# balloon-v06.net
KiCad netlist of a schematic drawn in EAGLE
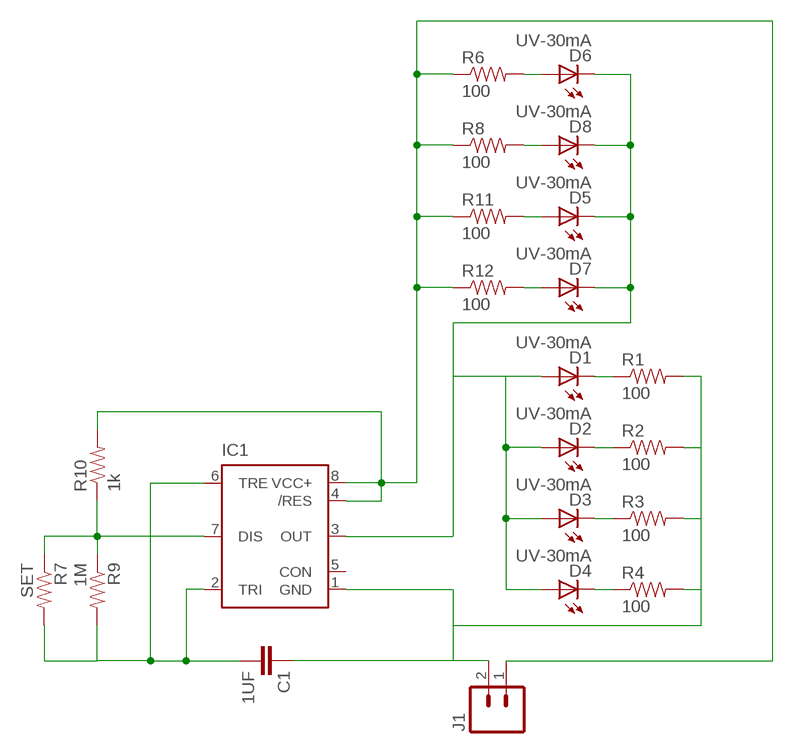
[diagram p0: schematic, sheet 1]

(export (version "E")
  (design (tool "Eeschema 10.0.6"))
  (components
    (comp (ref "C1")
      (value "1UF")
      (footprint "eagle-import:0603-CAP")
      (libsource (lib "eagle-import") (part "CAP0603-CAP"))
    )
    (comp (ref "D1")
      (value "UV-30mA")
      (footprint "eagle-import:CHIPLED_0603")
      (libsource (lib "eagle-import") (part "LEDCHIPLED_0603"))
    )
    (comp (ref "D2")
      (value "UV-30mA")
      (footprint "eagle-import:CHIPLED_0603")
      (libsource (lib "eagle-import") (part "LEDCHIPLED_0603"))
    )
    (comp (ref "D3")
      (value "UV-30mA")
      (footprint "eagle-import:CHIPLED_0603")
      (libsource (lib "eagle-import") (part "LEDCHIPLED_0603"))
    )
    (comp (ref "D4")
      (value "UV-30mA")
      (footprint "eagle-import:CHIPLED_0603")
      (libsource (lib "eagle-import") (part "LEDCHIPLED_0603"))
    )
    (comp (ref "D5")
      (value "UV-30mA")
      (footprint "eagle-import:CHIPLED_0603")
      (libsource (lib "eagle-import") (part "LEDCHIPLED_0603"))
    )
    (comp (ref "D6")
      (value "UV-30mA")
      (footprint "eagle-import:CHIPLED_0603")
      (libsource (lib "eagle-import") (part "LEDCHIPLED_0603"))
    )
    (comp (ref "D7")
      (value "UV-30mA")
      (footprint "eagle-import:CHIPLED_0603")
      (libsource (lib "eagle-import") (part "LEDCHIPLED_0603"))
    )
    (comp (ref "D8")
      (value "UV-30mA")
      (footprint "eagle-import:CHIPLED_0603")
      (libsource (lib "eagle-import") (part "LEDCHIPLED_0603"))
    )
    (comp (ref "IC1")
      (value "NE555D")
      (footprint "eagle-import:SO08")
      (libsource (lib "eagle-import") (part "NE555D"))
    )
    (comp (ref "J1")
      (value "M02PTH3")
      (footprint "eagle-import:1X02_LONGPADS")
      (libsource (lib "eagle-import") (part "M02PTH3"))
    )
    (comp (ref "R1")
      (value "100")
      (footprint "eagle-import:0603-RES")
      (libsource (lib "eagle-import") (part "RESISTOR0603-RES"))
    )
    (comp (ref "R2")
      (value "100")
      (footprint "eagle-import:0603-RES")
      (libsource (lib "eagle-import") (part "RESISTOR0603-RES"))
    )
    (comp (ref "R3")
      (value "100")
      (footprint "eagle-import:0603-RES")
      (libsource (lib "eagle-import") (part "RESISTOR0603-RES"))
    )
    (comp (ref "R4")
      (value "100")
      (footprint "eagle-import:0603-RES")
      (libsource (lib "eagle-import") (part "RESISTOR0603-RES"))
    )
    (comp (ref "R6")
      (value "100")
      (footprint "eagle-import:0603-RES")
      (libsource (lib "eagle-import") (part "RESISTOR0603-RES"))
    )
    (comp (ref "R7")
      (value "SET")
      (footprint "eagle-import:0603-RES")
      (libsource (lib "eagle-import") (part "RESISTOR0603"))
    )
    (comp (ref "R8")
      (value "100")
      (footprint "eagle-import:0603-RES")
      (libsource (lib "eagle-import") (part "RESISTOR0603-RES"))
    )
    (comp (ref "R9")
      (value "1M")
      (footprint "eagle-import:0603-RES")
      (libsource (lib "eagle-import") (part "RESISTOR0603-RES"))
    )
    (comp (ref "R10")
      (value "1k")
      (footprint "eagle-import:0603-RES")
      (libsource (lib "eagle-import") (part "RESISTOR0603-RES"))
    )
    (comp (ref "R11")
      (value "100")
      (footprint "eagle-import:0603-RES")
      (libsource (lib "eagle-import") (part "RESISTOR0603-RES"))
    )
    (comp (ref "R12")
      (value "100")
      (footprint "eagle-import:0603-RES")
      (libsource (lib "eagle-import") (part "RESISTOR0603-RES"))
    )
  )
  (nets
    (net (code "1") (name "Net-(D1-PadC)") (class "Default")
      (node (ref "D1") (pin "C") (pinfunction "C_C") (pintype "passive"))
      (node (ref "R1") (pin "1") (pinfunction "1_1") (pintype "passive"))
    )
    (net (code "2") (name "Net-(D2-PadC)") (class "Default")
      (node (ref "D2") (pin "C") (pinfunction "C_C") (pintype "passive"))
      (node (ref "R2") (pin "1") (pinfunction "1_1") (pintype "passive"))
    )
    (net (code "3") (name "Net-(D3-PadC)") (class "Default")
      (node (ref "D3") (pin "C") (pinfunction "C_C") (pintype "passive"))
      (node (ref "R3") (pin "1") (pinfunction "1_1") (pintype "passive"))
    )
    (net (code "4") (name "Net-(D4-PadC)") (class "Default")
      (node (ref "D4") (pin "C") (pinfunction "C_C") (pintype "passive"))
      (node (ref "R4") (pin "1") (pinfunction "1_1") (pintype "passive"))
    )
    (net (code "5") (name "Net-(D5-PadA)") (class "Default")
      (node (ref "D5") (pin "A") (pinfunction "A_A") (pintype "passive"))
      (node (ref "R11") (pin "2") (pinfunction "2_2") (pintype "passive"))
    )
    (net (code "6") (name "Net-(D6-PadA)") (class "Default")
      (node (ref "D6") (pin "A") (pinfunction "A_A") (pintype "passive"))
      (node (ref "R6") (pin "2") (pinfunction "2_2") (pintype "passive"))
    )
    (net (code "7") (name "Net-(D7-PadA)") (class "Default")
      (node (ref "D7") (pin "A") (pinfunction "A_A") (pintype "passive"))
      (node (ref "R12") (pin "2") (pinfunction "2_2") (pintype "passive"))
    )
    (net (code "8") (name "Net-(D8-PadA)") (class "Default")
      (node (ref "D8") (pin "A") (pinfunction "A_A") (pintype "passive"))
      (node (ref "R8") (pin "2") (pinfunction "2_2") (pintype "passive"))
    )
    (net (code "9") (name "Net-(IC1-DIS)") (class "Default")
      (node (ref "IC1") (pin "7") (pinfunction "DIS_7") (pintype "input"))
      (node (ref "R10") (pin "1") (pinfunction "1_1") (pintype "passive"))
      (node (ref "R7") (pin "1") (pinfunction "1_1") (pintype "passive"))
      (node (ref "R9") (pin "1") (pinfunction "1_1") (pintype "passive"))
    )
    (net (code "10") (name "Net-(IC1-GND)") (class "Default")
      (node (ref "C1") (pin "1") (pinfunction "1_1") (pintype "passive"))
      (node (ref "IC1") (pin "1") (pinfunction "GND_1") (pintype "power_in"))
      (node (ref "J1") (pin "2") (pinfunction "2_2") (pintype "passive"))
      (node (ref "R1") (pin "2") (pinfunction "2_2") (pintype "passive"))
      (node (ref "R2") (pin "2") (pinfunction "2_2") (pintype "passive"))
      (node (ref "R3") (pin "2") (pinfunction "2_2") (pintype "passive"))
      (node (ref "R4") (pin "2") (pinfunction "2_2") (pintype "passive"))
    )
    (net (code "11") (name "Net-(IC1-OUT)") (class "Default")
      (node (ref "D1") (pin "A") (pinfunction "A_A") (pintype "passive"))
      (node (ref "D2") (pin "A") (pinfunction "A_A") (pintype "passive"))
      (node (ref "D3") (pin "A") (pinfunction "A_A") (pintype "passive"))
      (node (ref "D4") (pin "A") (pinfunction "A_A") (pintype "passive"))
      (node (ref "D5") (pin "C") (pinfunction "C_C") (pintype "passive"))
      (node (ref "D6") (pin "C") (pinfunction "C_C") (pintype "passive"))
      (node (ref "D7") (pin "C") (pinfunction "C_C") (pintype "passive"))
      (node (ref "D8") (pin "C") (pinfunction "C_C") (pintype "passive"))
      (node (ref "IC1") (pin "3") (pinfunction "OUT_3") (pintype "output"))
    )
    (net (code "12") (name "Net-(IC1-TRE)") (class "Default")
      (node (ref "C1") (pin "2") (pinfunction "2_2") (pintype "passive"))
      (node (ref "IC1") (pin "2") (pinfunction "TRI_2") (pintype "input"))
      (node (ref "IC1") (pin "6") (pinfunction "TRE_6") (pintype "input"))
      (node (ref "R7") (pin "2") (pinfunction "2_2") (pintype "passive"))
      (node (ref "R9") (pin "2") (pinfunction "2_2") (pintype "passive"))
    )
    (net (code "13") (name "Net-(IC1-VCC+)") (class "Default")
      (node (ref "IC1") (pin "4") (pinfunction "/RES_4") (pintype "input"))
      (node (ref "IC1") (pin "8") (pinfunction "VCC+_8") (pintype "power_in"))
      (node (ref "J1") (pin "1") (pinfunction "1_1") (pintype "passive"))
      (node (ref "R10") (pin "2") (pinfunction "2_2") (pintype "passive"))
      (node (ref "R11") (pin "1") (pinfunction "1_1") (pintype "passive"))
      (node (ref "R12") (pin "1") (pinfunction "1_1") (pintype "passive"))
      (node (ref "R6") (pin "1") (pinfunction "1_1") (pintype "passive"))
      (node (ref "R8") (pin "1") (pinfunction "1_1") (pintype "passive"))
    )
    (net (code "14") (name "unconnected-(IC1-CON-Pad5)") (class "Default")
      (node (ref "IC1") (pin "5") (pinfunction "CON_5") (pintype "input"))
    )
  )
)
